# MCU.net
KiCad netlist of a schematic drawn in Altium Designer
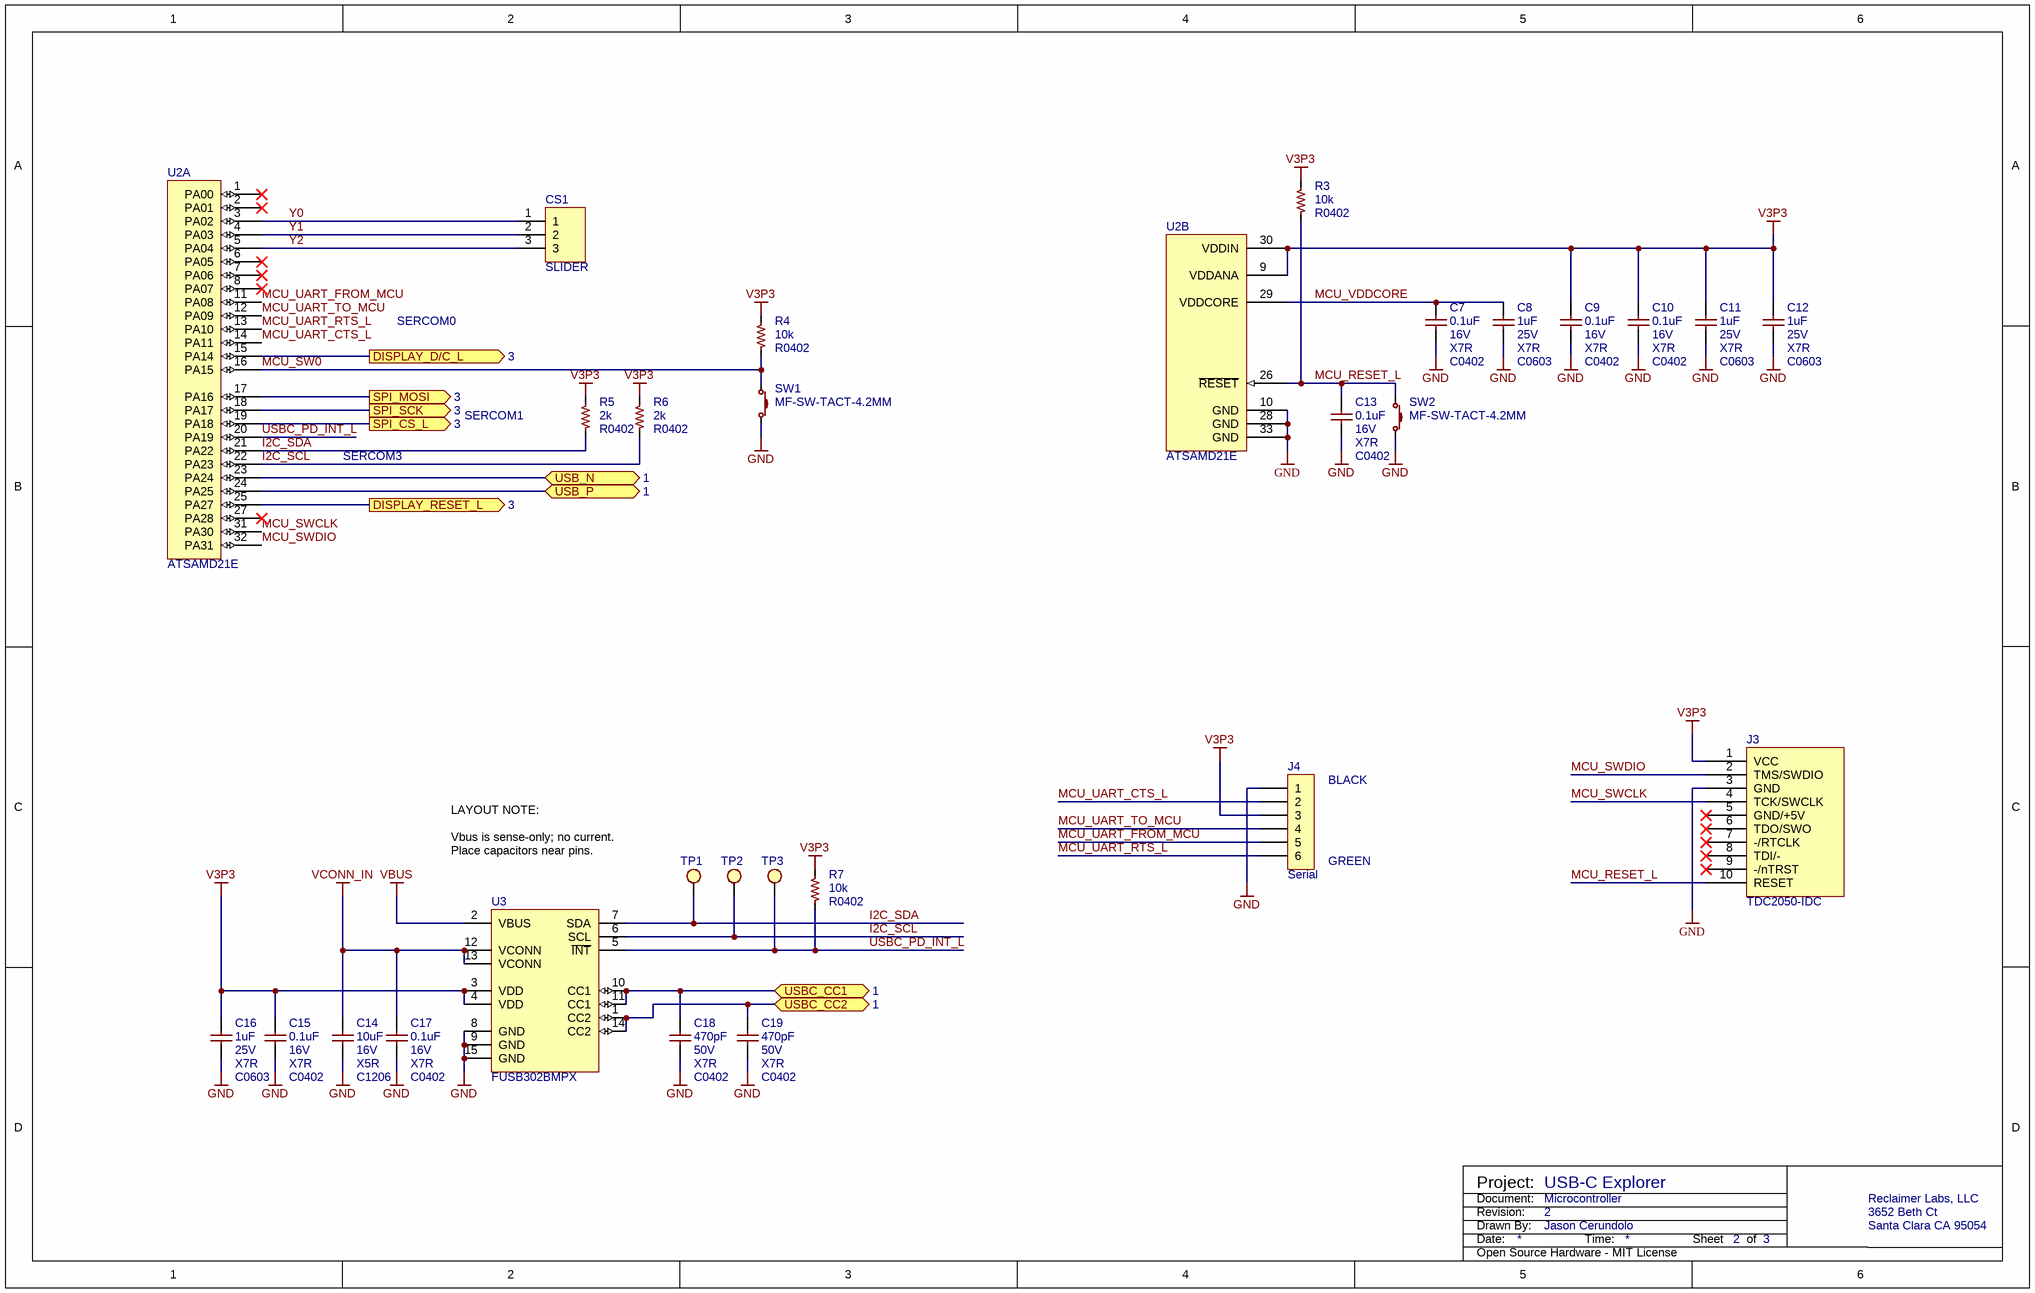
[diagram p0: MCU.schdoc]

(export (version "E")
  (design (tool "Eeschema 10.0.6"))
  (components
    (comp (ref "C7")
      (value "0.1uF")
      (footprint "ReclaimerLabs:C0402")
      (fields
        (field (name "VOLTAGE") "16V")
        (field (name "MATERIAL") "X7R")
        (field (name "Comment") "MF-CAP-0402-0.1uF")
      )
      (libsource (lib "ReclaimerLabs") (part "CAPACITOR_NP"))
    )
    (comp (ref "C8")
      (value "1uF")
      (footprint "C0603")
      (fields
        (field (name "VOLTAGE") "25V")
        (field (name "MATERIAL") "X7R")
        (field (name "Comment") "MF-CAP-0603-1uF")
      )
      (libsource (lib "ReclaimerLabs") (part "CAPACITOR_NP"))
    )
    (comp (ref "C9")
      (value "0.1uF")
      (footprint "ReclaimerLabs:C0402")
      (fields
        (field (name "VOLTAGE") "16V")
        (field (name "MATERIAL") "X7R")
        (field (name "Comment") "MF-CAP-0402-0.1uF")
      )
      (libsource (lib "ReclaimerLabs") (part "CAPACITOR_NP"))
    )
    (comp (ref "C10")
      (value "0.1uF")
      (footprint "ReclaimerLabs:C0402")
      (fields
        (field (name "VOLTAGE") "16V")
        (field (name "MATERIAL") "X7R")
        (field (name "Comment") "MF-CAP-0402-0.1uF")
      )
      (libsource (lib "ReclaimerLabs") (part "CAPACITOR_NP"))
    )
    (comp (ref "C11")
      (value "1uF")
      (footprint "C0603")
      (fields
        (field (name "VOLTAGE") "25V")
        (field (name "MATERIAL") "X7R")
        (field (name "Comment") "MF-CAP-0603-1uF")
      )
      (libsource (lib "ReclaimerLabs") (part "CAPACITOR_NP"))
    )
    (comp (ref "C12")
      (value "1uF")
      (footprint "C0603")
      (fields
        (field (name "VOLTAGE") "25V")
        (field (name "MATERIAL") "X7R")
        (field (name "Comment") "MF-CAP-0603-1uF")
      )
      (libsource (lib "ReclaimerLabs") (part "CAPACITOR_NP"))
    )
    (comp (ref "C13")
      (value "0.1uF")
      (footprint "ReclaimerLabs:C0402")
      (fields
        (field (name "VOLTAGE") "16V")
        (field (name "MATERIAL") "X7R")
        (field (name "Comment") "MF-CAP-0402-0.1uF")
      )
      (libsource (lib "ReclaimerLabs") (part "CAPACITOR_NP"))
    )
    (comp (ref "C14")
      (value "10uF")
      (footprint "C1206")
      (fields
        (field (name "VOLTAGE") "16V")
        (field (name "MATERIAL") "X5R")
        (field (name "Comment") "MF-CAP-1206-10uF")
      )
      (libsource (lib "ReclaimerLabs") (part "CAPACITOR_NP"))
    )
    (comp (ref "C15")
      (value "0.1uF")
      (footprint "ReclaimerLabs:C0402")
      (fields
        (field (name "VOLTAGE") "16V")
        (field (name "MATERIAL") "X7R")
        (field (name "Comment") "MF-CAP-0402-0.1uF")
      )
      (libsource (lib "ReclaimerLabs") (part "CAPACITOR_NP"))
    )
    (comp (ref "C16")
      (value "1uF")
      (footprint "C0603")
      (fields
        (field (name "VOLTAGE") "25V")
        (field (name "MATERIAL") "X7R")
        (field (name "Comment") "MF-CAP-0603-1uF")
      )
      (libsource (lib "ReclaimerLabs") (part "CAPACITOR_NP"))
    )
    (comp (ref "C17")
      (value "0.1uF")
      (footprint "ReclaimerLabs:C0402")
      (fields
        (field (name "VOLTAGE") "16V")
        (field (name "MATERIAL") "X7R")
        (field (name "Comment") "MF-CAP-0402-0.1uF")
      )
      (libsource (lib "ReclaimerLabs") (part "CAPACITOR_NP"))
    )
    (comp (ref "C18")
      (value "470pF")
      (footprint "C0402")
      (fields
        (field (name "VOLTAGE") "50V")
        (field (name "MATERIAL") "X7R")
        (field (name "Comment") "CL05B471KB5NNNC")
      )
      (libsource (lib "ReclaimerLabs") (part "CAPACITOR_NP"))
    )
    (comp (ref "C19")
      (value "470pF")
      (footprint "C0402")
      (fields
        (field (name "VOLTAGE") "50V")
        (field (name "MATERIAL") "X7R")
        (field (name "Comment") "CL05B471KB5NNNC")
      )
      (libsource (lib "ReclaimerLabs") (part "CAPACITOR_NP"))
    )
    (comp (ref "CS1")
      (value "SLIDER")
      (footprint "QTOUCH_SLIDER_19x6mm")
      (libsource (lib "ReclaimerLabs") (part "QTOUCH_SLIDER"))
    )
    (comp (ref "J3")
      (value "TDC2050-IDC")
      (footprint "TC2050-IDC-NL")
      (fields (field (name "Comment") "DNP"))
      (libsource (lib "ReclaimerLabs") (part "TC2050-IDC"))
    )
    (comp (ref "J4")
      (value "Serial")
      (footprint "CONN_HEADER_01x06_2mm54_Straight")
      (fields (field (name "Comment") "DNP"))
      (libsource (lib "ReclaimerLabs") (part "CONN_HEADER_01x06_2mm54_Straight"))
    )
    (comp (ref "R3")
      (value "10k")
      (footprint "ReclaimerLabs:R0402")
      (fields (field (name "Comment") "MF-RES-0402-10K"))
      (libsource (lib "ReclaimerLabs") (part "RESISTOR"))
    )
    (comp (ref "R4")
      (value "10k")
      (footprint "ReclaimerLabs:R0402")
      (fields (field (name "Comment") "MF-RES-0402-10K"))
      (libsource (lib "ReclaimerLabs") (part "RESISTOR"))
    )
    (comp (ref "R5")
      (value "2k")
      (footprint "ReclaimerLabs:R0402")
      (fields (field (name "Comment") "MF-RES-0402-2K"))
      (libsource (lib "ReclaimerLabs") (part "RESISTOR"))
    )
    (comp (ref "R6")
      (value "2k")
      (footprint "ReclaimerLabs:R0402")
      (fields (field (name "Comment") "MF-RES-0402-2K"))
      (libsource (lib "ReclaimerLabs") (part "RESISTOR"))
    )
    (comp (ref "R7")
      (value "10k")
      (footprint "ReclaimerLabs:R0402")
      (fields (field (name "Comment") "MF-RES-0402-10K"))
      (libsource (lib "ReclaimerLabs") (part "RESISTOR"))
    )
    (comp (ref "SW1")
      (value "MF-SW-TACT-4.2MM")
      (footprint "TACT_4.2MM")
      (libsource (lib "ReclaimerLabs") (part "SW_SPST_PB"))
    )
    (comp (ref "SW2")
      (value "MF-SW-TACT-4.2MM")
      (footprint "TACT_4.2MM")
      (libsource (lib "ReclaimerLabs") (part "SW_SPST_PB"))
    )
    (comp (ref "TP1")
      (value "TESTPOINT")
      (footprint "TP_1mm")
      (libsource (lib "ReclaimerLabs") (part "TESTPOINT"))
    )
    (comp (ref "TP2")
      (value "TESTPOINT")
      (footprint "TP_1mm")
      (libsource (lib "ReclaimerLabs") (part "TESTPOINT"))
    )
    (comp (ref "TP3")
      (value "TESTPOINT")
      (footprint "TP_1mm")
      (libsource (lib "ReclaimerLabs") (part "TESTPOINT"))
    )
    (comp (ref "U2")
      (value "ATSAMD21E")
      (footprint "QFN32EP")
      (fields (field (name "Comment") "ATSAMD21E17A-MU"))
      (libsource (lib "") (part "ATSAMD21E_1"))
    )
    (comp (ref "U3")
      (value "FUSB302BMPX")
      (footprint "MLP14")
      (libsource (lib "ReclaimerLabs") (part "FUSB302B"))
    )
  )
  (nets
    (net (code "1") (name "/DISPLAY_D{slash}C_L") (class "Default")
      (node (ref "U2") (pin "15") (pinfunction "PA14_15") (pintype "bidirectional"))
    )
    (net (code "2") (name "/DISPLAY_RESET_L") (class "Default")
      (node (ref "U2") (pin "25") (pinfunction "PA27_25") (pintype "bidirectional"))
    )
    (net (code "3") (name "/I2C_SCL") (class "Default")
      (node (ref "R6") (pin "2") (pinfunction "R2_2") (pintype "passive"))
      (node (ref "TP2") (pin "1") (pinfunction "1_1") (pintype "passive"))
      (node (ref "U2") (pin "22") (pinfunction "PA23_22") (pintype "bidirectional"))
      (node (ref "U3") (pin "6") (pinfunction "SCL_6") (pintype "open_collector"))
    )
    (net (code "4") (name "/I2C_SDA") (class "Default")
      (node (ref "R5") (pin "2") (pinfunction "R2_2") (pintype "passive"))
      (node (ref "TP1") (pin "1") (pinfunction "1_1") (pintype "passive"))
      (node (ref "U2") (pin "21") (pinfunction "PA22_21") (pintype "bidirectional"))
      (node (ref "U3") (pin "7") (pinfunction "SDA_7") (pintype "open_collector"))
    )
    (net (code "5") (name "/MCU_RESET_L") (class "Default")
      (node (ref "C13") (pin "1") (pinfunction "C1_1") (pintype "passive"))
      (node (ref "J3") (pin "10") (pinfunction "RESET_10") (pintype "passive"))
      (node (ref "R3") (pin "2") (pinfunction "R2_2") (pintype "passive"))
      (node (ref "SW2") (pin "1") (pinfunction "1_1") (pintype "power_in"))
      (node (ref "U2") (pin "26") (pinfunction "~{RESET}_26") (pintype "input"))
    )
    (net (code "6") (name "/MCU_SW0") (class "Default")
      (node (ref "R4") (pin "2") (pinfunction "R2_2") (pintype "passive"))
      (node (ref "SW1") (pin "1") (pinfunction "1_1") (pintype "power_in"))
      (node (ref "U2") (pin "16") (pinfunction "PA15_16") (pintype "bidirectional"))
    )
    (net (code "7") (name "/MCU_SWCLK") (class "Default")
      (node (ref "J3") (pin "4") (pinfunction "TCK/SWCLK_4") (pintype "passive"))
      (node (ref "U2") (pin "31") (pinfunction "PA30_31") (pintype "bidirectional"))
    )
    (net (code "8") (name "/MCU_SWDIO") (class "Default")
      (node (ref "J3") (pin "2") (pinfunction "TMS/SWDIO_2") (pintype "passive"))
      (node (ref "U2") (pin "32") (pinfunction "PA31_32") (pintype "bidirectional"))
    )
    (net (code "9") (name "/MCU_UART_CTS_L") (class "Default")
      (node (ref "J4") (pin "2") (pinfunction "2_2") (pintype "passive"))
      (node (ref "U2") (pin "14") (pinfunction "PA11_14") (pintype "bidirectional"))
    )
    (net (code "10") (name "/MCU_UART_FROM_MCU") (class "Default")
      (node (ref "J4") (pin "5") (pinfunction "5_5") (pintype "passive"))
      (node (ref "U2") (pin "11") (pinfunction "PA08_11") (pintype "bidirectional"))
    )
    (net (code "11") (name "/MCU_UART_RTS_L") (class "Default")
      (node (ref "J4") (pin "6") (pinfunction "6_6") (pintype "passive"))
      (node (ref "U2") (pin "13") (pinfunction "PA10_13") (pintype "bidirectional"))
    )
    (net (code "12") (name "/MCU_UART_TO_MCU") (class "Default")
      (node (ref "J4") (pin "4") (pinfunction "4_4") (pintype "passive"))
      (node (ref "U2") (pin "12") (pinfunction "PA09_12") (pintype "bidirectional"))
    )
    (net (code "13") (name "/MCU_VDDCORE") (class "Default")
      (node (ref "C7") (pin "1") (pinfunction "C1_1") (pintype "passive"))
      (node (ref "C8") (pin "1") (pinfunction "C1_1") (pintype "passive"))
      (node (ref "U2") (pin "29") (pinfunction "VDDCORE_29") (pintype "power_in"))
    )
    (net (code "14") (name "/SPI_CS_L") (class "Default")
      (node (ref "U2") (pin "19") (pinfunction "PA18_19") (pintype "bidirectional"))
    )
    (net (code "15") (name "/SPI_MOSI") (class "Default")
      (node (ref "U2") (pin "17") (pinfunction "PA16_17") (pintype "bidirectional"))
    )
    (net (code "16") (name "/SPI_SCK") (class "Default")
      (node (ref "U2") (pin "18") (pinfunction "PA17_18") (pintype "bidirectional"))
    )
    (net (code "17") (name "/USBC_CC1") (class "Default")
      (node (ref "C18") (pin "1") (pinfunction "C1_1") (pintype "passive"))
      (node (ref "U3") (pin "10") (pinfunction "CC1_10") (pintype "bidirectional"))
      (node (ref "U3") (pin "11") (pinfunction "CC1_11") (pintype "bidirectional"))
    )
    (net (code "18") (name "/USBC_CC2") (class "Default")
      (node (ref "C19") (pin "1") (pinfunction "C1_1") (pintype "passive"))
      (node (ref "U3") (pin "1") (pinfunction "CC2_1") (pintype "bidirectional"))
      (node (ref "U3") (pin "14") (pinfunction "CC2_14") (pintype "bidirectional"))
    )
    (net (code "19") (name "/USBC_PD_INT_L") (class "Default")
      (node (ref "R7") (pin "2") (pinfunction "R2_2") (pintype "passive"))
      (node (ref "TP3") (pin "1") (pinfunction "1_1") (pintype "passive"))
      (node (ref "U2") (pin "20") (pinfunction "PA19_20") (pintype "bidirectional"))
      (node (ref "U3") (pin "5") (pinfunction "~{INT}_5") (pintype "open_collector"))
    )
    (net (code "20") (name "/USB_N") (class "Default")
      (node (ref "U2") (pin "23") (pinfunction "PA24_23") (pintype "bidirectional"))
    )
    (net (code "21") (name "/USB_P") (class "Default")
      (node (ref "U2") (pin "24") (pinfunction "PA25_24") (pintype "bidirectional"))
    )
    (net (code "22") (name "/Y0") (class "Default")
      (node (ref "CS1") (pin "1") (pinfunction "1_1") (pintype "power_in"))
      (node (ref "U2") (pin "3") (pinfunction "PA02_3") (pintype "bidirectional"))
    )
    (net (code "23") (name "/Y1") (class "Default")
      (node (ref "CS1") (pin "2") (pinfunction "2_2") (pintype "power_in"))
      (node (ref "U2") (pin "4") (pinfunction "PA03_4") (pintype "bidirectional"))
    )
    (net (code "24") (name "/Y2") (class "Default")
      (node (ref "CS1") (pin "3") (pinfunction "3_3") (pintype "power_in"))
      (node (ref "U2") (pin "5") (pinfunction "PA04_5") (pintype "bidirectional"))
    )
    (net (code "25") (name "GND") (class "Default")
      (node (ref "C10") (pin "2") (pinfunction "C2_2") (pintype "passive"))
      (node (ref "C11") (pin "2") (pinfunction "C2_2") (pintype "passive"))
      (node (ref "C12") (pin "2") (pinfunction "C2_2") (pintype "passive"))
      (node (ref "C13") (pin "2") (pinfunction "C2_2") (pintype "passive"))
      (node (ref "C14") (pin "2") (pinfunction "C2_2") (pintype "passive"))
      (node (ref "C15") (pin "2") (pinfunction "C2_2") (pintype "passive"))
      (node (ref "C16") (pin "2") (pinfunction "C2_2") (pintype "passive"))
      (node (ref "C17") (pin "2") (pinfunction "C2_2") (pintype "passive"))
      (node (ref "C18") (pin "2") (pinfunction "C2_2") (pintype "passive"))
      (node (ref "C19") (pin "2") (pinfunction "C2_2") (pintype "passive"))
      (node (ref "C7") (pin "2") (pinfunction "C2_2") (pintype "passive"))
      (node (ref "C8") (pin "2") (pinfunction "C2_2") (pintype "passive"))
      (node (ref "C9") (pin "2") (pinfunction "C2_2") (pintype "passive"))
      (node (ref "J3") (pin "3") (pinfunction "GND_3") (pintype "passive"))
      (node (ref "J4") (pin "1") (pinfunction "1_1") (pintype "passive"))
      (node (ref "SW1") (pin "2") (pinfunction "2_2") (pintype "power_in"))
      (node (ref "SW2") (pin "2") (pinfunction "2_2") (pintype "power_in"))
      (node (ref "U2") (pin "10") (pinfunction "GND_10") (pintype "passive"))
      (node (ref "U2") (pin "28") (pinfunction "GND_28") (pintype "passive"))
      (node (ref "U2") (pin "33") (pinfunction "GND_33") (pintype "passive"))
      (node (ref "U3") (pin "15") (pinfunction "GND_15") (pintype "passive"))
      (node (ref "U3") (pin "8") (pinfunction "GND_8") (pintype "passive"))
      (node (ref "U3") (pin "9") (pinfunction "GND_9") (pintype "passive"))
    )
    (net (code "26") (name "V3P3") (class "Default")
      (node (ref "C10") (pin "1") (pinfunction "C1_1") (pintype "passive"))
      (node (ref "C11") (pin "1") (pinfunction "C1_1") (pintype "passive"))
      (node (ref "C12") (pin "1") (pinfunction "C1_1") (pintype "passive"))
      (node (ref "C15") (pin "1") (pinfunction "C1_1") (pintype "passive"))
      (node (ref "C16") (pin "1") (pinfunction "C1_1") (pintype "passive"))
      (node (ref "C9") (pin "1") (pinfunction "C1_1") (pintype "passive"))
      (node (ref "J3") (pin "1") (pinfunction "VCC_1") (pintype "passive"))
      (node (ref "J4") (pin "3") (pinfunction "3_3") (pintype "passive"))
      (node (ref "R3") (pin "1") (pinfunction "R1_1") (pintype "passive"))
      (node (ref "R4") (pin "1") (pinfunction "R1_1") (pintype "passive"))
      (node (ref "R5") (pin "1") (pinfunction "R1_1") (pintype "passive"))
      (node (ref "R6") (pin "1") (pinfunction "R1_1") (pintype "passive"))
      (node (ref "R7") (pin "1") (pinfunction "R1_1") (pintype "passive"))
      (node (ref "U2") (pin "30") (pinfunction "VDDIN_30") (pintype "power_in"))
      (node (ref "U2") (pin "9") (pinfunction "VDDANA_9") (pintype "power_in"))
      (node (ref "U3") (pin "3") (pinfunction "VDD_3") (pintype "power_in"))
      (node (ref "U3") (pin "4") (pinfunction "VDD_4") (pintype "power_in"))
    )
    (net (code "27") (name "VBUS") (class "Default")
      (node (ref "U3") (pin "2") (pinfunction "VBUS_2") (pintype "power_in"))
    )
    (net (code "28") (name "VCONN_IN") (class "Default")
      (node (ref "C14") (pin "1") (pinfunction "C1_1") (pintype "passive"))
      (node (ref "C17") (pin "1") (pinfunction "C1_1") (pintype "passive"))
      (node (ref "U3") (pin "12") (pinfunction "VCONN_12") (pintype "power_in"))
      (node (ref "U3") (pin "13") (pinfunction "VCONN_13") (pintype "power_in"))
    )
    (net (code "29") (name "unconnected-(J3--{slash}RTCLK-Pad7)") (class "Default")
      (node (ref "J3") (pin "7") (pinfunction "-/RTCLK_7") (pintype "passive+no_connect"))
    )
    (net (code "30") (name "unconnected-(J3--{slash}nTRST-Pad9)") (class "Default")
      (node (ref "J3") (pin "9") (pinfunction "-/nTRST_9") (pintype "passive+no_connect"))
    )
    (net (code "31") (name "unconnected-(J3-GND{slash}+5V-Pad5)") (class "Default")
      (node (ref "J3") (pin "5") (pinfunction "GND/+5V_5") (pintype "passive+no_connect"))
    )
    (net (code "32") (name "unconnected-(J3-TDI{slash}--Pad8)") (class "Default")
      (node (ref "J3") (pin "8") (pinfunction "TDI/-_8") (pintype "passive+no_connect"))
    )
    (net (code "33") (name "unconnected-(J3-TDO{slash}SWO-Pad6)") (class "Default")
      (node (ref "J3") (pin "6") (pinfunction "TDO/SWO_6") (pintype "passive+no_connect"))
    )
    (net (code "34") (name "unconnected-(U2A-PA00-Pad1)") (class "Default")
      (node (ref "U2") (pin "1") (pinfunction "PA00_1") (pintype "bidirectional+no_connect"))
    )
    (net (code "35") (name "unconnected-(U2A-PA01-Pad2)") (class "Default")
      (node (ref "U2") (pin "2") (pinfunction "PA01_2") (pintype "bidirectional+no_connect"))
    )
    (net (code "36") (name "unconnected-(U2A-PA05-Pad6)") (class "Default")
      (node (ref "U2") (pin "6") (pinfunction "PA05_6") (pintype "bidirectional+no_connect"))
    )
    (net (code "37") (name "unconnected-(U2A-PA06-Pad7)") (class "Default")
      (node (ref "U2") (pin "7") (pinfunction "PA06_7") (pintype "bidirectional+no_connect"))
    )
    (net (code "38") (name "unconnected-(U2A-PA07-Pad8)") (class "Default")
      (node (ref "U2") (pin "8") (pinfunction "PA07_8") (pintype "bidirectional+no_connect"))
    )
    (net (code "39") (name "unconnected-(U2A-PA28-Pad27)") (class "Default")
      (node (ref "U2") (pin "27") (pinfunction "PA28_27") (pintype "bidirectional+no_connect"))
    )
  )
)
